# Buzzer.net
KiCad netlist of a schematic drawn in Altium Designer
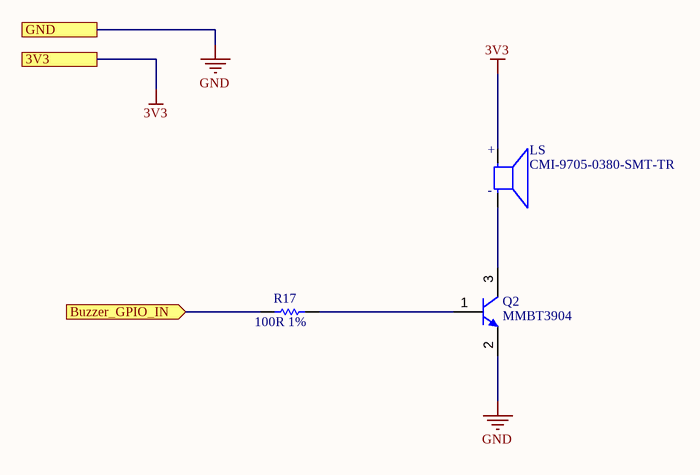
[diagram p0: Buzzer.SchDoc]

(export (version "E")
  (design (tool "Eeschema 10.0.6"))
  (components
    (comp (ref "LS")
      (value "CMI-9705-0380-SMT-TR")
      (footprint "SnapEDApcb:CUI_CMI-9705-0380-SMT-TR")
      (description "9.7 mm, 3 Vdc, 80 dB, Surface Mount, Driving Circuit, Magnetic Audio Indicator Buzzer")
      (fields (field (name "MF") "CUI Devices"))
      (libsource (lib "SnapEDAsch") (part "CMI-9705-0380-SMT-TR"))
    )
    (comp (ref "Q2")
      (value "MMBT3904")
      (footprint "INF-SOT23_L")
      (description "NPN Silicon Switching Transistor, 40 V VCEO, 200 mA IC, SOT23, Reel, Green")
      (fields (field (name "MANUFACTURER") "Infineon"))
      (libsource (lib "Altium Content Vault") (part "INF-BJTNPN-BEC-3"))
    )
    (comp (ref "R17")
      (value "100R 1%")
      (footprint "RESC0603(1608)_N")
      (description "100R 0.1W 1% 0603 (1608 Metric)  SMD")
      (fields (field (name "TOLERANCE") "1 %") (field (name "POWER") "0.1 W"))
      (libsource (lib "Altium Content Vault") (part "RES"))
    )
  )
  (nets
    (net (code "1") (name "/Buzzer_GPIO_IN") (class "Default")
      (node (ref "R17") (pin "1") (pinfunction "1_1") (pintype "passive"))
    )
    (net (code "2") (name "3V3") (class "Default")
      (node (ref "LS") (pin "P") (pinfunction "P_P") (pintype "passive"))
    )
    (net (code "3") (name "GND") (class "Default")
      (node (ref "Q2") (pin "2") (pinfunction "E_2") (pintype "passive"))
    )
    (net (code "4") (name "Net-(Q2-B)") (class "Default")
      (node (ref "Q2") (pin "1") (pinfunction "B_1") (pintype "passive"))
      (node (ref "R17") (pin "2") (pinfunction "2_2") (pintype "passive"))
    )
    (net (code "5") (name "Net-(Q2-C)") (class "Default")
      (node (ref "LS") (pin "N") (pinfunction "N_N") (pintype "passive"))
      (node (ref "Q2") (pin "3") (pinfunction "C_3") (pintype "passive"))
    )
  )
)
